# Led_Master.net
KiCad netlist of a schematic drawn in Altium Designer
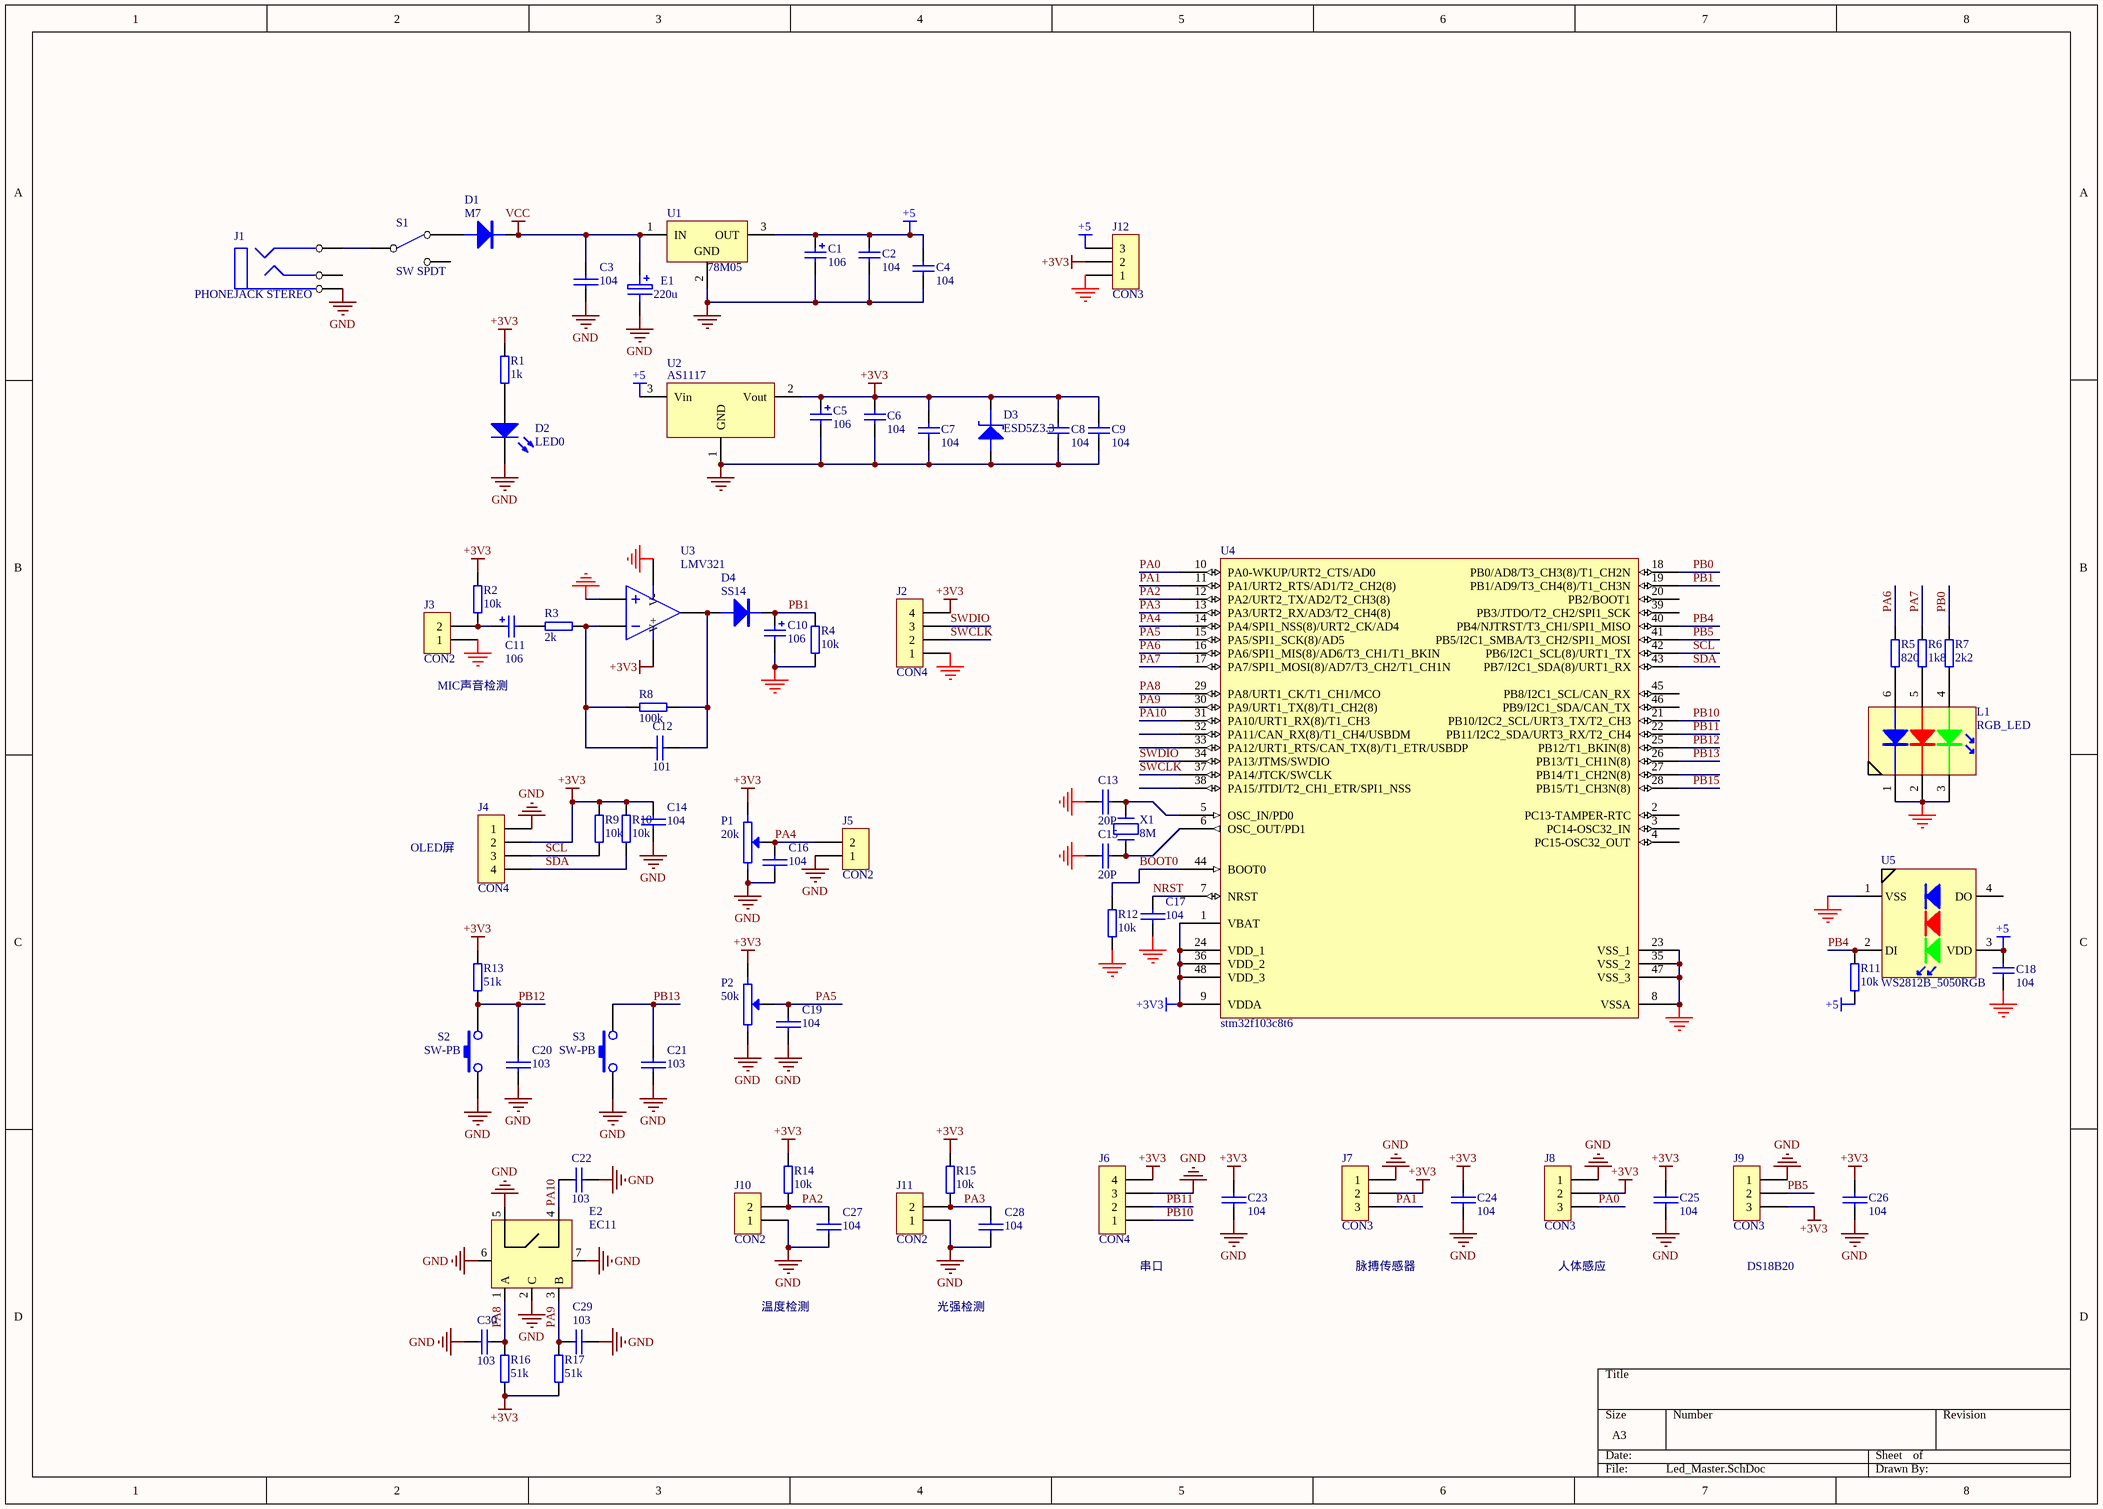
[diagram p0: Led_Master.SchDoc]

(export (version "E")
  (design (tool "Eeschema 10.0.6"))
  (components
    (comp (ref "C1")
      (value "106")
      (footprint "0603C")
      (description "Polarized Capacitor (Radial)")
      (fields (field (name "PUBLISHER") "Altium Limited"))
      (libsource (lib "*") (part "Cap Pol1"))
    )
    (comp (ref "C2")
      (value "104")
      (footprint "0603C")
      (description "Capacitor")
      (fields (field (name "PUBLISHER") "Altium Limited"))
      (libsource (lib "*") (part "Cap"))
    )
    (comp (ref "C3") (value "104") (footprint "0603c") (libsource (lib "*") (part "Pro14.tmp_104_7")))
    (comp (ref "C4")
      (value "104")
      (footprint "0603C")
      (description "Capacitor")
      (fields (field (name "PUBLISHER") "Altium Limited"))
      (libsource (lib "*") (part "Cap"))
    )
    (comp (ref "C5")
      (value "106")
      (footprint "0603C")
      (description "Polarized Capacitor (Radial)")
      (fields (field (name "PUBLISHER") "Altium Limited"))
      (libsource (lib "*") (part "Cap Pol1"))
    )
    (comp (ref "C6")
      (value "104")
      (footprint "0603C")
      (description "Capacitor")
      (fields (field (name "PUBLISHER") "Altium Limited"))
      (libsource (lib "*") (part "Cap"))
    )
    (comp (ref "C7")
      (value "104")
      (footprint "0603C")
      (description "Capacitor")
      (fields (field (name "PUBLISHER") "Altium Limited"))
      (libsource (lib "*") (part "Cap"))
    )
    (comp (ref "C8")
      (value "104")
      (footprint "0603C")
      (description "Capacitor")
      (fields (field (name "PUBLISHER") "Altium Limited"))
      (libsource (lib "*") (part "Cap"))
    )
    (comp (ref "C9")
      (value "104")
      (footprint "0603C")
      (description "Capacitor")
      (fields (field (name "PUBLISHER") "Altium Limited"))
      (libsource (lib "*") (part "Cap"))
    )
    (comp (ref "C10")
      (value "106")
      (footprint "0603C")
      (description "Polarized Capacitor (Radial)")
      (fields (field (name "PUBLISHER") "Altium Limited"))
      (libsource (lib "*") (part "Cap Pol1"))
    )
    (comp (ref "C11")
      (value "106")
      (footprint "0603C")
      (description "Polarized Capacitor (Radial)")
      (fields (field (name "PUBLISHER") "Altium Limited"))
      (libsource (lib "*") (part "Cap Pol1"))
    )
    (comp (ref "C12")
      (value "101")
      (footprint "0603c")
      (description "Capacitor")
      (libsource (lib "*") (part "CAP"))
    )
    (comp (ref "C13") (value "20P") (footprint "0603c") (libsource (lib "*") (part "Pro87.tmp_22p_18")))
    (comp (ref "C14") (value "104") (footprint "0603c") (libsource (lib "*") (part "Pro14.tmp_104_7")))
    (comp (ref "C15") (value "20P") (footprint "0603c") (libsource (lib "*") (part "Pro87.tmp_22p_18")))
    (comp (ref "C16") (value "104") (footprint "0603c") (libsource (lib "*") (part "Pro14.tmp_104_7")))
    (comp (ref "C17")
      (value "104")
      (footprint "0603c")
      (description "Capacitor")
      (libsource (lib "*") (part "CAP"))
    )
    (comp (ref "C18")
      (value "104")
      (footprint "0603C")
      (description "Capacitor")
      (fields (field (name "PUBLISHER") "Altium Limited"))
      (libsource (lib "*") (part "Cap"))
    )
    (comp (ref "C19") (value "104") (footprint "0603c") (libsource (lib "*") (part "Pro14.tmp_104_7")))
    (comp (ref "C20") (value "103") (footprint "0603c") (libsource (lib "*") (part "Pro14.tmp_104_7")))
    (comp (ref "C21") (value "103") (footprint "0603c") (libsource (lib "*") (part "Pro14.tmp_104_7")))
    (comp (ref "C22") (value "103") (footprint "0603c") (libsource (lib "*") (part "Pro14.tmp_104_7")))
    (comp (ref "C23")
      (value "104")
      (footprint "0603c")
      (description "Capacitor")
      (libsource (lib "*") (part "CAP"))
    )
    (comp (ref "C24")
      (value "104")
      (footprint "0603c")
      (description "Capacitor")
      (libsource (lib "*") (part "CAP"))
    )
    (comp (ref "C25")
      (value "104")
      (footprint "0603c")
      (description "Capacitor")
      (libsource (lib "*") (part "CAP"))
    )
    (comp (ref "C26")
      (value "104")
      (footprint "0603c")
      (description "Capacitor")
      (libsource (lib "*") (part "CAP"))
    )
    (comp (ref "C27") (value "104") (footprint "0603c") (libsource (lib "*") (part "Pro14.tmp_104_7")))
    (comp (ref "C28") (value "104") (footprint "0603c") (libsource (lib "*") (part "Pro14.tmp_104_7")))
    (comp (ref "C29") (value "103") (footprint "0603c") (libsource (lib "*") (part "Pro14.tmp_104_7")))
    (comp (ref "C30") (value "103") (footprint "0603c") (libsource (lib "*") (part "Pro14.tmp_104_7")))
    (comp (ref "D1")
      (value "M7")
      (footprint "DO214_SMA")
      (description "Diode")
      (libsource (lib "*") (part "DIODE"))
    )
    (comp (ref "D2")
      (value "LED0")
      (footprint "LED_0805_R")
      (description "Typical INFRARED GaAs LED")
      (fields (field (name "PUBLISHER") "Altium Limited"))
      (libsource (lib "JL_SCH") (part "LED0"))
    )
    (comp (ref "D3")
      (value "ESD5Z3.3")
      (footprint "SOD323")
      (description "Zener Diode")
      (libsource (lib "*") (part "ZENER2"))
    )
    (comp (ref "D4")
      (value "SS14")
      (footprint "SOD123")
      (description "Diode")
      (libsource (lib "*") (part "DIODE"))
    )
    (comp (ref "E1")
      (value "220u")
      (footprint "CAP_PR_2.5_8")
      (libsource (lib "*") (part "Pro87.tmp_47u_10"))
    )
    (comp (ref "E2")
      (value "EC11")
      (footprint "SW_EC11")
      (description "EC11编码开关")
      (libsource (lib "mySchlib") (part "EC11编码开关"))
    )
    (comp (ref "J1")
      (value "PHONEJACK STEREO")
      (footprint "内径5.5插座")
      (libsource (lib "Miscellaneous Devices") (part "PHONEJACK STEREO"))
    )
    (comp (ref "J2")
      (value "CON4")
      (footprint "SIP4")
      (description "Connector")
      (libsource (lib "*") (part "CON4"))
    )
    (comp (ref "J3")
      (value "CON2")
      (footprint "SIP02")
      (description "Connector")
      (libsource (lib "Miscellaneous Devices") (part "CON2"))
    )
    (comp (ref "J4")
      (value "CON4")
      (footprint "OLED 1.3寸屏")
      (description "Connector")
      (libsource (lib "") (part "CON4_1"))
    )
    (comp (ref "J5")
      (value "CON2")
      (footprint "SIP02")
      (description "Connector")
      (libsource (lib "") (part "CON2_1"))
    )
    (comp (ref "J6")
      (value "CON4")
      (footprint "XH_2.54_4P")
      (description "Connector")
      (libsource (lib "*") (part "CON4"))
    )
    (comp (ref "J7")
      (value "CON3")
      (footprint "SIP03")
      (description "Connector")
      (libsource (lib "Miscellaneous Devices") (part "CON3"))
    )
    (comp (ref "J8")
      (value "CON3")
      (footprint "SIP03")
      (description "Connector")
      (libsource (lib "Miscellaneous Devices") (part "CON3"))
    )
    (comp (ref "J9")
      (value "CON3")
      (footprint "SIP03")
      (description "Connector")
      (libsource (lib "Miscellaneous Devices") (part "CON3"))
    )
    (comp (ref "J10")
      (value "CON2")
      (footprint "SIP02")
      (description "Connector")
      (libsource (lib "Miscellaneous Devices") (part "CON2"))
    )
    (comp (ref "J11")
      (value "CON2")
      (footprint "SIP02")
      (description "Connector")
      (libsource (lib "Miscellaneous Devices") (part "CON2"))
    )
    (comp (ref "J12")
      (value "CON3")
      (footprint "SIP03")
      (description "Connector")
      (libsource (lib "") (part "CON3_1"))
    )
    (comp (ref "L1")
      (value "RGB_LED")
      (footprint "Miscellaneous Devices.~(5):LED_5050")
      (libsource (lib "mySchlib") (part "RGB_LED"))
    )
    (comp (ref "P1")
      (value "20k")
      (footprint "RV0932")
      (description "Potentiometer")
      (libsource (lib "Miscellaneous Devices") (part "POT2"))
    )
    (comp (ref "P2")
      (value "50k")
      (footprint "RV0932")
      (description "Potentiometer")
      (libsource (lib "Miscellaneous Devices") (part "POT2"))
    )
    (comp (ref "R1") (value "1k") (footprint "0603r") (libsource (lib "*") (part "RES2")))
    (comp (ref "R2") (value "10k") (footprint "0603r") (libsource (lib "*") (part "RES2")))
    (comp (ref "R3") (value "2k") (footprint "0603r") (libsource (lib "*") (part "RES2")))
    (comp (ref "R4") (value "10k") (footprint "0603r") (libsource (lib "*") (part "RES2")))
    (comp (ref "R5") (value "820") (footprint "0603r") (libsource (lib "*") (part "RES2")))
    (comp (ref "R6") (value "1k8") (footprint "0603r") (libsource (lib "*") (part "RES2")))
    (comp (ref "R7") (value "2k2") (footprint "0603r") (libsource (lib "*") (part "RES2")))
    (comp (ref "R8") (value "100k") (footprint "0603r") (libsource (lib "*") (part "RES2")))
    (comp (ref "R9") (value "10k") (footprint "0603r") (libsource (lib "*") (part "RES2")))
    (comp (ref "R10") (value "10k") (footprint "0603r") (libsource (lib "*") (part "RES2")))
    (comp (ref "R11") (value "10k") (footprint "0603r") (libsource (lib "*") (part "RES2")))
    (comp (ref "R12") (value "10k") (footprint "0603r") (libsource (lib "*") (part "RES2")))
    (comp (ref "R13") (value "51k") (footprint "0603r") (libsource (lib "*") (part "RES2")))
    (comp (ref "R14") (value "10k") (footprint "0603r") (libsource (lib "*") (part "RES2")))
    (comp (ref "R15") (value "10k") (footprint "0603r") (libsource (lib "*") (part "RES2")))
    (comp (ref "R16") (value "51k") (footprint "0603r") (libsource (lib "*") (part "RES2")))
    (comp (ref "R17") (value "51k") (footprint "0603r") (libsource (lib "*") (part "RES2")))
    (comp (ref "S1")
      (value "SW SPDT")
      (footprint "SS12D10直脚拨动开关")
      (libsource (lib "Miscellaneous Devices") (part "SW SPDT"))
    )
    (comp (ref "S2")
      (value "SW-PB")
      (footprint "SW_PB_6X6")
      (libsource (lib "Miscellaneous Devices") (part "SW-PB"))
    )
    (comp (ref "S3")
      (value "SW-PB")
      (footprint "SW_PB_6X6")
      (libsource (lib "Miscellaneous Devices") (part "SW-PB"))
    )
    (comp (ref "U1")
      (value "78M05")
      (footprint "TO-252AA")
      (description "Series of Adjustable Micropower Voltage Regulators")
      (fields
        (field (name "PARTNUMBER") "LP2950CDT-5.0")
        (field (name "MANUFACTURER") "National Semiconductor")
        (field (name "PUBLISHER") "Altium Limited")
      )
      (libsource (lib "NSC LDO") (part "LP2950CDT-5.0"))
    )
    (comp (ref "U2") (value "AS1117") (footprint "SOT223") (libsource (lib "*") (part "VOLTREG1")))
    (comp (ref "U3")
      (value "LMV321")
      (footprint "SOT23_5")
      (description "Operational Amplifier")
      (libsource (lib "*") (part "OPAMP"))
    )
    (comp (ref "U4")
      (value "stm32f103c8t6")
      (footprint "LQFP_48_7X7")
      (libsource (lib "mySchlib") (part "stm32f103_48p"))
    )
    (comp (ref "U5")
      (value "WS2812B_5050RGB")
      (footprint "LED_5050")
      (libsource (lib "mySchlib") (part "WS2812B_5050RGB"))
    )
    (comp (ref "X1") (value "8M") (footprint "CAPM5032X12N") (libsource (lib "*") (part "Pro87.tmp_8M_17")))
  )
  (nets
    (net (code "1") (name "+3V3") (class "Default")
      (node (ref "C14") (pin "1") (pintype "passive"))
      (node (ref "C23") (pin "2") (pinfunction "2_2") (pintype "passive"))
      (node (ref "C24") (pin "2") (pinfunction "2_2") (pintype "passive"))
      (node (ref "C25") (pin "2") (pinfunction "2_2") (pintype "passive"))
      (node (ref "C26") (pin "2") (pinfunction "2_2") (pintype "passive"))
      (node (ref "C5") (pin "1") (pinfunction "1_1") (pintype "passive"))
      (node (ref "C6") (pin "1") (pinfunction "1_1") (pintype "passive"))
      (node (ref "C7") (pin "1") (pinfunction "1_1") (pintype "passive"))
      (node (ref "C8") (pin "1") (pinfunction "1_1") (pintype "passive"))
      (node (ref "C9") (pin "1") (pinfunction "1_1") (pintype "passive"))
      (node (ref "D3") (pin "2") (pinfunction "K_2") (pintype "passive"))
      (node (ref "J12") (pin "2") (pinfunction "2_2") (pintype "passive"))
      (node (ref "J2") (pin "4") (pinfunction "4_4") (pintype "passive"))
      (node (ref "J4") (pin "2") (pinfunction "2_2") (pintype "passive"))
      (node (ref "J6") (pin "4") (pinfunction "4_4") (pintype "passive"))
      (node (ref "J7") (pin "2") (pinfunction "2_2") (pintype "passive"))
      (node (ref "J8") (pin "2") (pinfunction "2_2") (pintype "passive"))
      (node (ref "J9") (pin "3") (pinfunction "3_3") (pintype "passive"))
      (node (ref "P1") (pin "2") (pinfunction "2_2") (pintype "passive"))
      (node (ref "P2") (pin "2") (pinfunction "2_2") (pintype "passive"))
      (node (ref "R1") (pin "2") (pinfunction "2_2") (pintype "passive"))
      (node (ref "R10") (pin "2") (pinfunction "2_2") (pintype "passive"))
      (node (ref "R13") (pin "2") (pinfunction "2_2") (pintype "passive"))
      (node (ref "R14") (pin "2") (pinfunction "2_2") (pintype "passive"))
      (node (ref "R15") (pin "2") (pinfunction "2_2") (pintype "passive"))
      (node (ref "R16") (pin "1") (pinfunction "1_1") (pintype "passive"))
      (node (ref "R17") (pin "1") (pinfunction "1_1") (pintype "passive"))
      (node (ref "R2") (pin "2") (pinfunction "2_2") (pintype "passive"))
      (node (ref "R9") (pin "2") (pinfunction "2_2") (pintype "passive"))
      (node (ref "U2") (pin "2") (pinfunction "Vout_2") (pintype "passive"))
      (node (ref "U3") (pin "4") (pinfunction "V+_4") (pintype "passive"))
      (node (ref "U4") (pin "1") (pinfunction "VBAT_1") (pintype "power_in"))
      (node (ref "U4") (pin "24") (pinfunction "VDD_1_24") (pintype "power_in"))
      (node (ref "U4") (pin "36") (pinfunction "VDD_2_36") (pintype "power_in"))
      (node (ref "U4") (pin "48") (pinfunction "VDD_3_48") (pintype "power_in"))
      (node (ref "U4") (pin "9") (pinfunction "VDDA_9") (pintype "power_in"))
    )
    (net (code "2") (name "+5") (class "Default")
      (node (ref "C1") (pin "1") (pinfunction "1_1") (pintype "passive"))
      (node (ref "C18") (pin "1") (pinfunction "1_1") (pintype "passive"))
      (node (ref "C2") (pin "1") (pinfunction "1_1") (pintype "passive"))
      (node (ref "C4") (pin "1") (pinfunction "1_1") (pintype "passive"))
      (node (ref "J12") (pin "3") (pinfunction "3_3") (pintype "passive"))
      (node (ref "R11") (pin "2") (pinfunction "2_2") (pintype "passive"))
      (node (ref "U1") (pin "3") (pinfunction "OUT_3") (pintype "power_in"))
      (node (ref "U2") (pin "3") (pinfunction "Vin_3") (pintype "passive"))
      (node (ref "U5") (pin "3") (pinfunction "VDD_3") (pintype "passive"))
    )
    (net (code "3") (name "/BOOT0") (class "Default")
      (node (ref "R12") (pin "2") (pinfunction "2_2") (pintype "passive"))
      (node (ref "U4") (pin "44") (pinfunction "BOOT0_44") (pintype "input"))
    )
    (net (code "4") (name "/NRST") (class "Default")
      (node (ref "C17") (pin "1") (pinfunction "1_1") (pintype "passive"))
      (node (ref "U4") (pin "7") (pinfunction "NRST_7") (pintype "bidirectional"))
    )
    (net (code "5") (name "/PA0") (class "Default")
      (node (ref "J8") (pin "3") (pinfunction "3_3") (pintype "passive"))
      (node (ref "U4") (pin "10") (pinfunction "PA0-WKUP/URT2_CTS/AD0_10") (pintype "bidirectional"))
    )
    (net (code "6") (name "/PA1") (class "Default")
      (node (ref "J7") (pin "3") (pinfunction "3_3") (pintype "passive"))
      (node (ref "U4") (pin "11") (pinfunction "PA1/URT2_RTS/AD1/T2_CH2(8)_11") (pintype "bidirectional"))
    )
    (net (code "7") (name "/PA2") (class "Default")
      (node (ref "C27") (pin "1") (pintype "passive"))
      (node (ref "J10") (pin "2") (pinfunction "2_2") (pintype "passive"))
      (node (ref "R14") (pin "1") (pinfunction "1_1") (pintype "passive"))
      (node (ref "U4") (pin "12") (pinfunction "PA2/URT2_TX/AD2/T2_CH3(8)_12") (pintype "bidirectional"))
    )
    (net (code "8") (name "/PA3") (class "Default")
      (node (ref "C28") (pin "1") (pintype "passive"))
      (node (ref "J11") (pin "2") (pinfunction "2_2") (pintype "passive"))
      (node (ref "R15") (pin "1") (pinfunction "1_1") (pintype "passive"))
      (node (ref "U4") (pin "13") (pinfunction "PA3/URT2_RX/AD3/T2_CH4(8)_13") (pintype "bidirectional"))
    )
    (net (code "9") (name "/PA4") (class "Default")
      (node (ref "C16") (pin "1") (pintype "passive"))
      (node (ref "J5") (pin "2") (pinfunction "2_2") (pintype "passive"))
      (node (ref "P1") (pin "3") (pinfunction "W_3") (pintype "passive"))
      (node (ref "U4") (pin "14") (pinfunction "PA4/SPI1_NSS(8)/URT2_CK/AD4_14") (pintype "bidirectional"))
    )
    (net (code "10") (name "/PA5") (class "Default")
      (node (ref "C19") (pin "1") (pintype "passive"))
      (node (ref "P2") (pin "3") (pinfunction "W_3") (pintype "passive"))
      (node (ref "U4") (pin "15") (pinfunction "PA5/SPI1_SCK(8)/AD5_15") (pintype "bidirectional"))
    )
    (net (code "11") (name "/PA6") (class "Default")
      (node (ref "R5") (pin "2") (pinfunction "2_2") (pintype "passive"))
      (node (ref "U4") (pin "16") (pinfunction "PA6/SPI1_MIS(8)/AD6/T3_CH1/T1_BKIN_16") (pintype "bidirectional"))
    )
    (net (code "12") (name "/PA7") (class "Default")
      (node (ref "R6") (pin "2") (pinfunction "2_2") (pintype "passive"))
      (node (ref "U4") (pin "17") (pinfunction "PA7/SPI1_MOSI(8)/AD7/T3_CH2/T1_CH1N_17") (pintype "bidirectional"))
    )
    (net (code "13") (name "/PA8") (class "Default")
      (node (ref "C30") (pin "2") (pintype "passive"))
      (node (ref "E2") (pin "1") (pinfunction "A_1") (pintype "passive"))
      (node (ref "R16") (pin "2") (pinfunction "2_2") (pintype "passive"))
      (node (ref "U4") (pin "29") (pinfunction "PA8/URT1_CK/T1_CH1/MCO_29") (pintype "bidirectional"))
    )
    (net (code "14") (name "/PA9") (class "Default")
      (node (ref "C29") (pin "1") (pintype "passive"))
      (node (ref "E2") (pin "3") (pinfunction "B_3") (pintype "passive"))
      (node (ref "R17") (pin "2") (pinfunction "2_2") (pintype "passive"))
      (node (ref "U4") (pin "30") (pinfunction "PA9/URT1_TX(8)/T1_CH2(8)_30") (pintype "bidirectional"))
    )
    (net (code "15") (name "/PA10") (class "Default")
      (node (ref "C22") (pin "1") (pintype "passive"))
      (node (ref "E2") (pin "4") (pinfunction "4_4") (pintype "passive"))
      (node (ref "U4") (pin "31") (pinfunction "PA10/URT1_RX(8)/T1_CH3_31") (pintype "bidirectional"))
    )
    (net (code "16") (name "/PB0") (class "Default")
      (node (ref "R7") (pin "2") (pinfunction "2_2") (pintype "passive"))
      (node (ref "U4") (pin "18") (pinfunction "PB0/AD8/T3_CH3(8)/T1_CH2N_18") (pintype "bidirectional"))
    )
    (net (code "17") (name "/PB1") (class "Default")
      (node (ref "C10") (pin "1") (pinfunction "1_1") (pintype "passive"))
      (node (ref "D4") (pin "2") (pinfunction "K_2") (pintype "passive"))
      (node (ref "R4") (pin "2") (pinfunction "2_2") (pintype "passive"))
      (node (ref "U4") (pin "19") (pinfunction "PB1/AD9/T3_CH4(8)/T1_CH3N_19") (pintype "bidirectional"))
    )
    (net (code "18") (name "/PB4") (class "Default")
      (node (ref "R11") (pin "1") (pinfunction "1_1") (pintype "passive"))
      (node (ref "U4") (pin "40") (pinfunction "PB4/NJTRST/T3_CH1/SPI1_MISO_40") (pintype "bidirectional"))
      (node (ref "U5") (pin "2") (pinfunction "DI_2") (pintype "passive"))
    )
    (net (code "19") (name "/PB5") (class "Default")
      (node (ref "J9") (pin "2") (pinfunction "2_2") (pintype "passive"))
      (node (ref "U4") (pin "41") (pinfunction "PB5/I2C1_SMBA/T3_CH2/SPI1_MOSI_41") (pintype "bidirectional"))
    )
    (net (code "20") (name "/PB10") (class "Default")
      (node (ref "J6") (pin "1") (pinfunction "1_1") (pintype "passive"))
      (node (ref "U4") (pin "21") (pinfunction "PB10/I2C2_SCL/URT3_TX/T2_CH3_21") (pintype "bidirectional"))
    )
    (net (code "21") (name "/PB11") (class "Default")
      (node (ref "J6") (pin "2") (pinfunction "2_2") (pintype "passive"))
      (node (ref "U4") (pin "22") (pinfunction "PB11/I2C2_SDA/URT3_RX/T2_CH4_22") (pintype "bidirectional"))
    )
    (net (code "22") (name "/PB12") (class "Default")
      (node (ref "C20") (pin "1") (pintype "passive"))
      (node (ref "R13") (pin "1") (pinfunction "1_1") (pintype "passive"))
      (node (ref "S2") (pin "2") (pinfunction "2_2") (pintype "passive"))
      (node (ref "U4") (pin "25") (pinfunction "PB12/T1_BKIN(8)_25") (pintype "bidirectional"))
    )
    (net (code "23") (name "/PB13") (class "Default")
      (node (ref "C21") (pin "1") (pintype "passive"))
      (node (ref "S3") (pin "2") (pinfunction "2_2") (pintype "passive"))
      (node (ref "U4") (pin "26") (pinfunction "PB13/T1_CH1N(8)_26") (pintype "bidirectional"))
    )
    (net (code "24") (name "/PB15") (class "Default")
      (node (ref "U4") (pin "28") (pinfunction "PB15/T1_CH3N(8)_28") (pintype "bidirectional"))
    )
    (net (code "25") (name "/SCL") (class "Default")
      (node (ref "J4") (pin "3") (pinfunction "3_3") (pintype "passive"))
      (node (ref "R9") (pin "1") (pinfunction "1_1") (pintype "passive"))
      (node (ref "U4") (pin "42") (pinfunction "PB6/I2C1_SCL(8)/URT1_TX_42") (pintype "bidirectional"))
    )
    (net (code "26") (name "/SDA") (class "Default")
      (node (ref "J4") (pin "4") (pinfunction "4_4") (pintype "passive"))
      (node (ref "R10") (pin "1") (pinfunction "1_1") (pintype "passive"))
      (node (ref "U4") (pin "43") (pinfunction "PB7/I2C1_SDA(8)/URT1_RX_43") (pintype "bidirectional"))
    )
    (net (code "27") (name "/SWCLK") (class "Default")
      (node (ref "J2") (pin "2") (pinfunction "2_2") (pintype "passive"))
      (node (ref "U4") (pin "37") (pinfunction "PA14/JTCK/SWCLK_37") (pintype "bidirectional"))
    )
    (net (code "28") (name "/SWDIO") (class "Default")
      (node (ref "J2") (pin "3") (pinfunction "3_3") (pintype "passive"))
      (node (ref "U4") (pin "34") (pinfunction "PA13/JTMS/SWDIO_34") (pintype "bidirectional"))
    )
    (net (code "29") (name "GND") (class "Default")
      (node (ref "C1") (pin "2") (pinfunction "2_2") (pintype "passive"))
      (node (ref "C10") (pin "2") (pinfunction "2_2") (pintype "passive"))
      (node (ref "C13") (pin "1") (pintype "passive"))
      (node (ref "C14") (pin "2") (pintype "passive"))
      (node (ref "C15") (pin "1") (pintype "passive"))
      (node (ref "C16") (pin "2") (pintype "passive"))
      (node (ref "C17") (pin "2") (pinfunction "2_2") (pintype "passive"))
      (node (ref "C18") (pin "2") (pinfunction "2_2") (pintype "passive"))
      (node (ref "C19") (pin "2") (pintype "passive"))
      (node (ref "C2") (pin "2") (pinfunction "2_2") (pintype "passive"))
      (node (ref "C20") (pin "2") (pintype "passive"))
      (node (ref "C21") (pin "2") (pintype "passive"))
      (node (ref "C22") (pin "2") (pintype "passive"))
      (node (ref "C23") (pin "1") (pinfunction "1_1") (pintype "passive"))
      (node (ref "C24") (pin "1") (pinfunction "1_1") (pintype "passive"))
      (node (ref "C25") (pin "1") (pinfunction "1_1") (pintype "passive"))
      (node (ref "C26") (pin "1") (pinfunction "1_1") (pintype "passive"))
      (node (ref "C27") (pin "2") (pintype "passive"))
      (node (ref "C28") (pin "2") (pintype "passive"))
      (node (ref "C29") (pin "2") (pintype "passive"))
      (node (ref "C3") (pin "2") (pintype "passive"))
      (node (ref "C30") (pin "1") (pintype "passive"))
      (node (ref "C4") (pin "2") (pinfunction "2_2") (pintype "passive"))
      (node (ref "C5") (pin "2") (pinfunction "2_2") (pintype "passive"))
      (node (ref "C6") (pin "2") (pinfunction "2_2") (pintype "passive"))
      (node (ref "C7") (pin "2") (pinfunction "2_2") (pintype "passive"))
      (node (ref "C8") (pin "2") (pinfunction "2_2") (pintype "passive"))
      (node (ref "C9") (pin "2") (pinfunction "2_2") (pintype "passive"))
      (node (ref "D2") (pin "2") (pinfunction "K_2") (pintype "passive"))
      (node (ref "D3") (pin "1") (pinfunction "A_1") (pintype "passive"))
      (node (ref "E1") (pin "2") (pintype "passive"))
      (node (ref "E2") (pin "2") (pinfunction "C_2") (pintype "passive"))
      (node (ref "E2") (pin "5") (pinfunction "5_5") (pintype "passive"))
      (node (ref "E2") (pin "6") (pinfunction "6_6") (pintype "passive"))
      (node (ref "E2") (pin "7") (pinfunction "7_7") (pintype "passive"))
      (node (ref "J1") (pin "3") (pinfunction "C_3") (pintype "passive"))
      (node (ref "J10") (pin "1") (pinfunction "1_1") (pintype "passive"))
      (node (ref "J11") (pin "1") (pinfunction "1_1") (pintype "passive"))
      (node (ref "J12") (pin "1") (pinfunction "1_1") (pintype "passive"))
      (node (ref "J2") (pin "1") (pinfunction "1_1") (pintype "passive"))
      (node (ref "J3") (pin "1") (pinfunction "1_1") (pintype "passive"))
      (node (ref "J4") (pin "1") (pinfunction "1_1") (pintype "passive"))
      (node (ref "J5") (pin "1") (pinfunction "1_1") (pintype "passive"))
      (node (ref "J6") (pin "3") (pinfunction "3_3") (pintype "passive"))
      (node (ref "J7") (pin "1") (pinfunction "1_1") (pintype "passive"))
      (node (ref "J8") (pin "1") (pinfunction "1_1") (pintype "passive"))
      (node (ref "J9") (pin "1") (pinfunction "1_1") (pintype "passive"))
      (node (ref "L1") (pin "1") (pinfunction "1_1") (pintype "passive"))
      (node (ref "L1") (pin "2") (pinfunction "2_2") (pintype "passive"))
      (node (ref "L1") (pin "3") (pinfunction "3_3") (pintype "passive"))
      (node (ref "P1") (pin "1") (pinfunction "1_1") (pintype "passive"))
      (node (ref "P2") (pin "1") (pinfunction "1_1") (pintype "passive"))
      (node (ref "R12") (pin "1") (pinfunction "1_1") (pintype "passive"))
      (node (ref "R4") (pin "1") (pinfunction "1_1") (pintype "passive"))
      (node (ref "S2") (pin "1") (pinfunction "1_1") (pintype "passive"))
      (node (ref "S3") (pin "1") (pinfunction "1_1") (pintype "passive"))
      (node (ref "U1") (pin "2") (pinfunction "GND_2") (pintype "power_in"))
      (node (ref "U2") (pin "1") (pinfunction "GND_1") (pintype "passive"))
      (node (ref "U3") (pin "2") (pinfunction "IN+_2") (pintype "passive"))
      (node (ref "U3") (pin "5") (pinfunction "V-_5") (pintype "passive"))
      (node (ref "U4") (pin "23") (pinfunction "VSS_1_23") (pintype "power_in"))
      (node (ref "U4") (pin "35") (pinfunction "VSS_2_35") (pintype "power_in"))
      (node (ref "U4") (pin "47") (pinfunction "VSS_3_47") (pintype "power_in"))
      (node (ref "U4") (pin "8") (pinfunction "VSSA_8") (pintype "power_in"))
      (node (ref "U5") (pin "1") (pinfunction "VSS_1") (pintype "passive"))
    )
    (net (code "30") (name "Net-(C11-Pad1)") (class "Default")
      (node (ref "C11") (pin "1") (pinfunction "1_1") (pintype "passive"))
      (node (ref "J3") (pin "2") (pinfunction "2_2") (pintype "passive"))
      (node (ref "R2") (pin "1") (pinfunction "1_1") (pintype "passive"))
    )
    (net (code "31") (name "Net-(C11-Pad2)") (class "Default")
      (node (ref "C11") (pin "2") (pinfunction "2_2") (pintype "passive"))
      (node (ref "R3") (pin "1") (pinfunction "1_1") (pintype "passive"))
    )
    (net (code "32") (name "Net-(D1-A)") (class "Default")
      (node (ref "D1") (pin "1") (pinfunction "A_1") (pintype "passive"))
      (node (ref "S1") (pin "2") (pinfunction "NC_2") (pintype "passive"))
    )
    (net (code "33") (name "Net-(D2-A)") (class "Default")
      (node (ref "D2") (pin "1") (pinfunction "A_1") (pintype "passive"))
      (node (ref "R1") (pin "1") (pinfunction "1_1") (pintype "passive"))
    )
    (net (code "34") (name "Net-(D4-A)") (class "Default")
      (node (ref "C12") (pin "1") (pinfunction "1_1") (pintype "passive"))
      (node (ref "D4") (pin "1") (pinfunction "A_1") (pintype "passive"))
      (node (ref "R8") (pin "1") (pinfunction "1_1") (pintype "passive"))
      (node (ref "U3") (pin "3") (pinfunction "OUT_3") (pintype "passive"))
    )
    (net (code "35") (name "Net-(J1-A)") (class "Default")
      (node (ref "J1") (pin "1") (pinfunction "A_1") (pintype "passive"))
      (node (ref "S1") (pin "1") (pinfunction "COMMON_1") (pintype "passive"))
    )
    (net (code "36") (name "Net-(L1-Pad4)") (class "Default")
      (node (ref "L1") (pin "4") (pinfunction "4_4") (pintype "passive"))
      (node (ref "R7") (pin "1") (pinfunction "1_1") (pintype "passive"))
    )
    (net (code "37") (name "Net-(L1-Pad5)") (class "Default")
      (node (ref "L1") (pin "5") (pinfunction "5_5") (pintype "passive"))
      (node (ref "R6") (pin "1") (pinfunction "1_1") (pintype "passive"))
    )
    (net (code "38") (name "Net-(L1-Pad6)") (class "Default")
      (node (ref "L1") (pin "6") (pinfunction "6_6") (pintype "passive"))
      (node (ref "R5") (pin "1") (pinfunction "1_1") (pintype "passive"))
    )
    (net (code "39") (name "Net-(U3-IN-)") (class "Default")
      (node (ref "C12") (pin "2") (pinfunction "2_2") (pintype "passive"))
      (node (ref "R3") (pin "2") (pinfunction "2_2") (pintype "passive"))
      (node (ref "R8") (pin "2") (pinfunction "2_2") (pintype "passive"))
      (node (ref "U3") (pin "1") (pinfunction "IN-_1") (pintype "passive"))
    )
    (net (code "40") (name "Net-(U4-OSC_IN{slash}PD0)") (class "Default")
      (node (ref "C13") (pin "2") (pintype "passive"))
      (node (ref "U4") (pin "5") (pinfunction "OSC_IN/PD0_5") (pintype "input"))
      (node (ref "X1") (pin "2") (pintype "passive"))
    )
    (net (code "41") (name "Net-(U4-OSC_OUT{slash}PD1)") (class "Default")
      (node (ref "C15") (pin "2") (pintype "passive"))
      (node (ref "U4") (pin "6") (pinfunction "OSC_OUT/PD1_6") (pintype "output"))
      (node (ref "X1") (pin "1") (pintype "passive"))
    )
    (net (code "42") (name "VCC") (class "Default")
      (node (ref "C3") (pin "1") (pintype "passive"))
      (node (ref "D1") (pin "2") (pinfunction "K_2") (pintype "passive"))
      (node (ref "E1") (pin "1") (pintype "passive"))
      (node (ref "U1") (pin "1") (pinfunction "IN_1") (pintype "power_in"))
    )
    (net (code "43") (name "unconnected-(J1-B-Pad2)") (class "Default")
      (node (ref "J1") (pin "2") (pinfunction "B_2") (pintype "passive"))
    )
    (net (code "44") (name "unconnected-(L1-1-PadA)") (class "Default")
      (node (ref "L1") (pin "A") (pinfunction "1_A") (pintype "passive"))
    )
    (net (code "45") (name "unconnected-(S1-NO-Pad3)") (class "Default")
      (node (ref "S1") (pin "3") (pinfunction "NO_3") (pintype "passive"))
    )
    (net (code "46") (name "unconnected-(U4-PA11{slash}CAN_RX(8){slash}T1_CH4{slash}USBDM-Pad32)") (class "Default")
      (node (ref "U4") (pin "32") (pinfunction "PA11/CAN_RX(8)/T1_CH4/USBDM_32") (pintype "bidirectional"))
    )
    (net (code "47") (name "unconnected-(U4-PA12{slash}URT1_RTS{slash}CAN_TX(8){slash}T1_ETR{slash}USBDP-Pad33)") (class "Default")
      (node (ref "U4") (pin "33") (pinfunction "PA12/URT1_RTS/CAN_TX(8)/T1_ETR/USBDP_33") (pintype "bidirectional"))
    )
    (net (code "48") (name "unconnected-(U4-PA15{slash}JTDI{slash}T2_CH1_ETR{slash}SPI1_NSS-Pad38)") (class "Default")
      (node (ref "U4") (pin "38") (pinfunction "PA15/JTDI/T2_CH1_ETR/SPI1_NSS_38") (pintype "bidirectional"))
    )
    (net (code "49") (name "unconnected-(U4-PB2{slash}BOOT1-Pad20)") (class "Default")
      (node (ref "U4") (pin "20") (pinfunction "PB2/BOOT1_20") (pintype "bidirectional"))
    )
    (net (code "50") (name "unconnected-(U4-PB3{slash}JTDO{slash}T2_CH2{slash}SPI1_SCK-Pad39)") (class "Default")
      (node (ref "U4") (pin "39") (pinfunction "PB3/JTDO/T2_CH2/SPI1_SCK_39") (pintype "bidirectional"))
    )
    (net (code "51") (name "unconnected-(U4-PB8{slash}I2C1_SCL{slash}CAN_RX-Pad45)") (class "Default")
      (node (ref "U4") (pin "45") (pinfunction "PB8/I2C1_SCL/CAN_RX_45") (pintype "bidirectional"))
    )
    (net (code "52") (name "unconnected-(U4-PB9{slash}I2C1_SDA{slash}CAN_TX-Pad46)") (class "Default")
      (node (ref "U4") (pin "46") (pinfunction "PB9/I2C1_SDA/CAN_TX_46") (pintype "bidirectional"))
    )
    (net (code "53") (name "unconnected-(U4-PB14{slash}T1_CH2N(8)-Pad27)") (class "Default")
      (node (ref "U4") (pin "27") (pinfunction "PB14/T1_CH2N(8)_27") (pintype "bidirectional"))
    )
    (net (code "54") (name "unconnected-(U4-PC13-TAMPER-RTC-Pad2)") (class "Default")
      (node (ref "U4") (pin "2") (pinfunction "PC13-TAMPER-RTC_2") (pintype "bidirectional"))
    )
    (net (code "55") (name "unconnected-(U4-PC14-OSC32_IN-Pad3)") (class "Default")
      (node (ref "U4") (pin "3") (pinfunction "PC14-OSC32_IN_3") (pintype "bidirectional"))
    )
    (net (code "56") (name "unconnected-(U4-PC15-OSC32_OUT-Pad4)") (class "Default")
      (node (ref "U4") (pin "4") (pinfunction "PC15-OSC32_OUT_4") (pintype "bidirectional"))
    )
    (net (code "57") (name "unconnected-(U5-1-PadA)") (class "Default")
      (node (ref "U5") (pin "A") (pinfunction "1_A") (pintype "passive"))
    )
    (net (code "58") (name "unconnected-(U5-DO-Pad4)") (class "Default")
      (node (ref "U5") (pin "4") (pinfunction "DO_4") (pintype "passive"))
    )
  )
)
